# soapdis_schematic.net
KiCad netlist of a schematic drawn in EAGLE
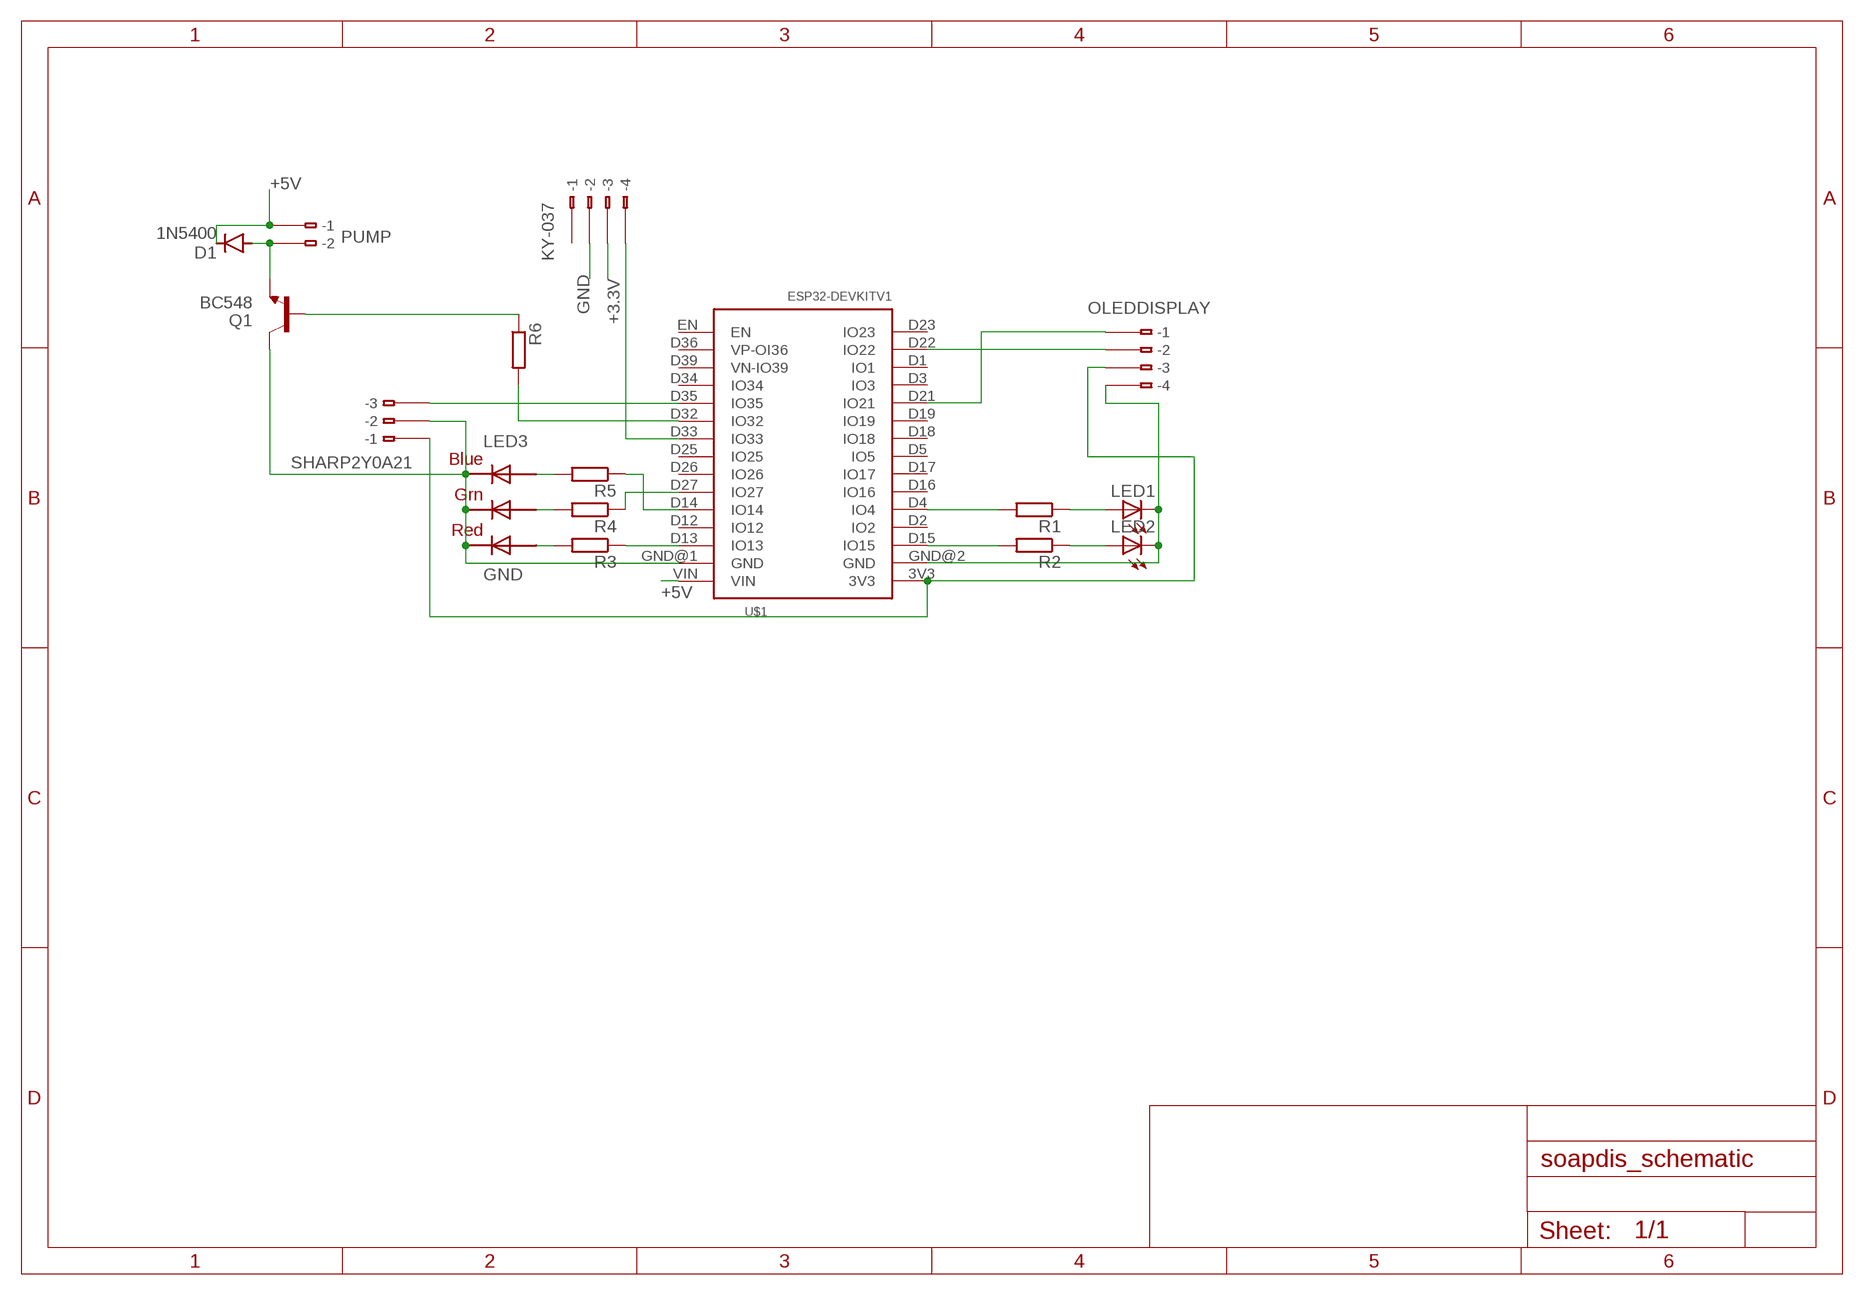
[diagram p0: schematic, sheet 1]

(export (version "E")
  (design (tool "Eeschema 10.0.6"))
  (components
    (comp (ref "D1")
      (value "1N5400")
      (footprint "eagle-import:DO201-15")
      (libsource (lib "eagle-import") (part "1N5400"))
    )
    (comp (ref "KY-037")
      (value "233-104")
      (footprint "eagle-import:233-104")
      (libsource (lib "eagle-import") (part "233-104"))
    )
    (comp (ref "LED1")
      (value "LED5MM")
      (footprint "eagle-import:LED5MM")
      (libsource (lib "eagle-import") (part "LED5MM"))
    )
    (comp (ref "LED2")
      (value "LED5MM")
      (footprint "eagle-import:LED5MM")
      (libsource (lib "eagle-import") (part "LED5MM"))
    )
    (comp (ref "LED3")
      (value "RGBLED5050")
      (footprint "eagle-import:RGBLED5050")
      (libsource (lib "eagle-import") (part "RGBLED5050"))
    )
    (comp (ref "OLEDDISPLAY")
      (value "233-104")
      (footprint "eagle-import:233-104")
      (libsource (lib "eagle-import") (part "233-104"))
    )
    (comp (ref "PUMP")
      (value "233-102")
      (footprint "eagle-import:233-102")
      (libsource (lib "eagle-import") (part "233-102"))
    )
    (comp (ref "Q1")
      (value "BC548")
      (footprint "eagle-import:TO92-EBC")
      (libsource (lib "eagle-import") (part "BC548"))
    )
    (comp (ref "R1")
      (value "R-EU_0204/7")
      (footprint "eagle-import:0204_7")
      (libsource (lib "eagle-import") (part "R-EU_0204/7"))
    )
    (comp (ref "R2")
      (value "R-EU_0204/7")
      (footprint "eagle-import:0204_7")
      (libsource (lib "eagle-import") (part "R-EU_0204/7"))
    )
    (comp (ref "R3")
      (value "R-EU_0204/7")
      (footprint "eagle-import:0204_7")
      (libsource (lib "eagle-import") (part "R-EU_0204/7"))
    )
    (comp (ref "R4")
      (value "R-EU_0204/7")
      (footprint "eagle-import:0204_7")
      (libsource (lib "eagle-import") (part "R-EU_0204/7"))
    )
    (comp (ref "R5")
      (value "R-EU_0204/7")
      (footprint "eagle-import:0204_7")
      (libsource (lib "eagle-import") (part "R-EU_0204/7"))
    )
    (comp (ref "R6")
      (value "R-EU_0204/7")
      (footprint "eagle-import:0204_7")
      (libsource (lib "eagle-import") (part "R-EU_0204/7"))
    )
    (comp (ref "SHARP2Y0A21")
      (value "233-103")
      (footprint "eagle-import:233-103")
      (libsource (lib "eagle-import") (part "233-103"))
    )
    (comp (ref "U$1")
      (value "ESP32DEVKITV1")
      (footprint "eagle-import:ESP32-DEVKITV1")
      (libsource (lib "eagle-import") (part "ESP32DEVKITV1"))
    )
  )
  (nets
    (net (code "1") (name "/+3.3V") (class "Default")
      (node (ref "KY-037") (pin "B3") (pinfunction "B-3_B3") (pintype "passive"))
    )
    (net (code "2") (name "/+5V") (class "Default")
      (node (ref "D1") (pin "C") (pinfunction "C_C") (pintype "passive"))
      (node (ref "PUMP") (pin "B1") (pinfunction "B-1_B1") (pintype "passive"))
      (node (ref "U$1") (pin "VIN") (pinfunction "VIN_VIN") (pintype "bidirectional"))
    )
    (net (code "3") (name "/GND") (class "Default")
      (node (ref "KY-037") (pin "B2") (pinfunction "B-2_B2") (pintype "passive"))
      (node (ref "LED3") (pin "4") (pinfunction "BLUE_C_4") (pintype "bidirectional"))
      (node (ref "LED3") (pin "5") (pinfunction "RED_C_5") (pintype "bidirectional"))
      (node (ref "LED3") (pin "6") (pinfunction "GREEN_C_6") (pintype "bidirectional"))
      (node (ref "Q1") (pin "C") (pinfunction "C_C") (pintype "passive"))
      (node (ref "SHARP2Y0A21") (pin "B2") (pinfunction "B-2_B2") (pintype "passive"))
      (node (ref "U$1") (pin "GND@1") (pinfunction "GND_GND@1") (pintype "bidirectional"))
    )
    (net (code "4") (name "Net-(KY-037-B-4)") (class "Default")
      (node (ref "KY-037") (pin "B4") (pinfunction "B-4_B4") (pintype "passive"))
      (node (ref "U$1") (pin "D33") (pinfunction "IO33_D33") (pintype "bidirectional"))
    )
    (net (code "5") (name "Net-(LED1-C)") (class "Default")
      (node (ref "LED1") (pin "K") (pinfunction "C_K") (pintype "passive"))
      (node (ref "LED2") (pin "K") (pinfunction "C_K") (pintype "passive"))
      (node (ref "OLEDDISPLAY") (pin "B4") (pinfunction "B-4_B4") (pintype "passive"))
      (node (ref "U$1") (pin "GND@2") (pinfunction "GND_GND@2") (pintype "bidirectional"))
    )
    (net (code "6") (name "Net-(LED1-PadA)") (class "Default")
      (node (ref "LED1") (pin "A") (pinfunction "A_A") (pintype "passive"))
      (node (ref "R1") (pin "1") (pinfunction "1_1") (pintype "passive"))
    )
    (net (code "7") (name "Net-(LED2-PadA)") (class "Default")
      (node (ref "LED2") (pin "A") (pinfunction "A_A") (pintype "passive"))
      (node (ref "R2") (pin "1") (pinfunction "1_1") (pintype "passive"))
    )
    (net (code "8") (name "Net-(LED3-BLUE_A)") (class "Default")
      (node (ref "LED3") (pin "3") (pinfunction "BLUE_A_3") (pintype "bidirectional"))
      (node (ref "R5") (pin "2") (pinfunction "2_2") (pintype "passive"))
    )
    (net (code "9") (name "Net-(LED3-GREEN_A)") (class "Default")
      (node (ref "LED3") (pin "1") (pinfunction "GREEN_A_1") (pintype "bidirectional"))
      (node (ref "R4") (pin "2") (pinfunction "2_2") (pintype "passive"))
    )
    (net (code "10") (name "Net-(LED3-RED_A)") (class "Default")
      (node (ref "LED3") (pin "2") (pinfunction "RED_A_2") (pintype "bidirectional"))
      (node (ref "R3") (pin "2") (pinfunction "2_2") (pintype "passive"))
    )
    (net (code "11") (name "Net-(OLEDDISPLAY-B-1)") (class "Default")
      (node (ref "OLEDDISPLAY") (pin "B1") (pinfunction "B-1_B1") (pintype "passive"))
      (node (ref "U$1") (pin "D21") (pinfunction "IO21_D21") (pintype "bidirectional"))
    )
    (net (code "12") (name "Net-(OLEDDISPLAY-B-2)") (class "Default")
      (node (ref "OLEDDISPLAY") (pin "B2") (pinfunction "B-2_B2") (pintype "passive"))
      (node (ref "U$1") (pin "D22") (pinfunction "IO22_D22") (pintype "bidirectional"))
    )
    (net (code "13") (name "Net-(OLEDDISPLAY-B-3)") (class "Default")
      (node (ref "OLEDDISPLAY") (pin "B3") (pinfunction "B-3_B3") (pintype "passive"))
      (node (ref "SHARP2Y0A21") (pin "B1") (pinfunction "B-1_B1") (pintype "passive"))
      (node (ref "U$1") (pin "3V3") (pinfunction "3V3_3V3") (pintype "bidirectional"))
    )
    (net (code "14") (name "Net-(PUMP-B-2)") (class "Default")
      (node (ref "D1") (pin "A") (pinfunction "A_A") (pintype "passive"))
      (node (ref "PUMP") (pin "B2") (pinfunction "B-2_B2") (pintype "passive"))
      (node (ref "Q1") (pin "E") (pinfunction "E_E") (pintype "passive"))
    )
    (net (code "15") (name "Net-(Q1-PadB)") (class "Default")
      (node (ref "Q1") (pin "B") (pinfunction "B_B") (pintype "passive"))
      (node (ref "R6") (pin "1") (pinfunction "1_1") (pintype "passive"))
    )
    (net (code "16") (name "Net-(SHARP2Y0A21-B-3)") (class "Default")
      (node (ref "SHARP2Y0A21") (pin "B3") (pinfunction "B-3_B3") (pintype "passive"))
      (node (ref "U$1") (pin "D35") (pinfunction "IO35_D35") (pintype "bidirectional"))
    )
    (net (code "17") (name "Net-(U$1-IO4)") (class "Default")
      (node (ref "R1") (pin "2") (pinfunction "2_2") (pintype "passive"))
      (node (ref "U$1") (pin "D4") (pinfunction "IO4_D4") (pintype "bidirectional"))
    )
    (net (code "18") (name "Net-(U$1-IO13)") (class "Default")
      (node (ref "R3") (pin "1") (pinfunction "1_1") (pintype "passive"))
      (node (ref "U$1") (pin "D13") (pinfunction "IO13_D13") (pintype "bidirectional"))
    )
    (net (code "19") (name "Net-(U$1-IO14)") (class "Default")
      (node (ref "R5") (pin "1") (pinfunction "1_1") (pintype "passive"))
      (node (ref "U$1") (pin "D14") (pinfunction "IO14_D14") (pintype "bidirectional"))
    )
    (net (code "20") (name "Net-(U$1-IO15)") (class "Default")
      (node (ref "R2") (pin "2") (pinfunction "2_2") (pintype "passive"))
      (node (ref "U$1") (pin "D15") (pinfunction "IO15_D15") (pintype "bidirectional"))
    )
    (net (code "21") (name "Net-(U$1-IO27)") (class "Default")
      (node (ref "R4") (pin "1") (pinfunction "1_1") (pintype "passive"))
      (node (ref "U$1") (pin "D27") (pinfunction "IO27_D27") (pintype "bidirectional"))
    )
    (net (code "22") (name "Net-(U$1-IO32)") (class "Default")
      (node (ref "R6") (pin "2") (pinfunction "2_2") (pintype "passive"))
      (node (ref "U$1") (pin "D32") (pinfunction "IO32_D32") (pintype "bidirectional"))
    )
    (net (code "23") (name "unconnected-(KY-037--1-PadA1)") (class "Default")
      (node (ref "KY-037") (pin "A1") (pinfunction "-1_A1") (pintype "passive"))
    )
    (net (code "24") (name "unconnected-(KY-037--2-PadA2)") (class "Default")
      (node (ref "KY-037") (pin "A2") (pinfunction "-2_A2") (pintype "passive"))
    )
    (net (code "25") (name "unconnected-(KY-037--3-PadA3)") (class "Default")
      (node (ref "KY-037") (pin "A3") (pinfunction "-3_A3") (pintype "passive"))
    )
    (net (code "26") (name "unconnected-(KY-037--4-PadA4)") (class "Default")
      (node (ref "KY-037") (pin "A4") (pinfunction "-4_A4") (pintype "passive"))
    )
    (net (code "27") (name "unconnected-(KY-037-B-1-PadB1)") (class "Default")
      (node (ref "KY-037") (pin "B1") (pinfunction "B-1_B1") (pintype "passive"))
    )
    (net (code "28") (name "unconnected-(OLEDDISPLAY--1-PadA1)") (class "Default")
      (node (ref "OLEDDISPLAY") (pin "A1") (pinfunction "-1_A1") (pintype "passive"))
    )
    (net (code "29") (name "unconnected-(OLEDDISPLAY--2-PadA2)") (class "Default")
      (node (ref "OLEDDISPLAY") (pin "A2") (pinfunction "-2_A2") (pintype "passive"))
    )
    (net (code "30") (name "unconnected-(OLEDDISPLAY--3-PadA3)") (class "Default")
      (node (ref "OLEDDISPLAY") (pin "A3") (pinfunction "-3_A3") (pintype "passive"))
    )
    (net (code "31") (name "unconnected-(OLEDDISPLAY--4-PadA4)") (class "Default")
      (node (ref "OLEDDISPLAY") (pin "A4") (pinfunction "-4_A4") (pintype "passive"))
    )
    (net (code "32") (name "unconnected-(PUMP--1-PadA1)") (class "Default")
      (node (ref "PUMP") (pin "A1") (pinfunction "-1_A1") (pintype "passive"))
    )
    (net (code "33") (name "unconnected-(PUMP--2-PadA2)") (class "Default")
      (node (ref "PUMP") (pin "A2") (pinfunction "-2_A2") (pintype "passive"))
    )
    (net (code "34") (name "unconnected-(SHARP2Y0A21--1-PadA1)") (class "Default")
      (node (ref "SHARP2Y0A21") (pin "A1") (pinfunction "-1_A1") (pintype "passive"))
    )
    (net (code "35") (name "unconnected-(SHARP2Y0A21--2-PadA2)") (class "Default")
      (node (ref "SHARP2Y0A21") (pin "A2") (pinfunction "-2_A2") (pintype "passive"))
    )
    (net (code "36") (name "unconnected-(SHARP2Y0A21--3-PadA3)") (class "Default")
      (node (ref "SHARP2Y0A21") (pin "A3") (pinfunction "-3_A3") (pintype "passive"))
    )
    (net (code "37") (name "unconnected-(U$1-IO1-PadD1)") (class "Default")
      (node (ref "U$1") (pin "D1") (pinfunction "IO1_D1") (pintype "bidirectional"))
    )
    (net (code "38") (name "unconnected-(U$1-IO2-PadD2)") (class "Default")
      (node (ref "U$1") (pin "D2") (pinfunction "IO2_D2") (pintype "bidirectional"))
    )
    (net (code "39") (name "unconnected-(U$1-IO3-PadD3)") (class "Default")
      (node (ref "U$1") (pin "D3") (pinfunction "IO3_D3") (pintype "bidirectional"))
    )
    (net (code "40") (name "unconnected-(U$1-IO5-PadD5)") (class "Default")
      (node (ref "U$1") (pin "D5") (pinfunction "IO5_D5") (pintype "bidirectional"))
    )
    (net (code "41") (name "unconnected-(U$1-IO12-PadD12)") (class "Default")
      (node (ref "U$1") (pin "D12") (pinfunction "IO12_D12") (pintype "bidirectional"))
    )
    (net (code "42") (name "unconnected-(U$1-IO16-PadD16)") (class "Default")
      (node (ref "U$1") (pin "D16") (pinfunction "IO16_D16") (pintype "bidirectional"))
    )
    (net (code "43") (name "unconnected-(U$1-IO17-PadD17)") (class "Default")
      (node (ref "U$1") (pin "D17") (pinfunction "IO17_D17") (pintype "bidirectional"))
    )
    (net (code "44") (name "unconnected-(U$1-IO18-PadD18)") (class "Default")
      (node (ref "U$1") (pin "D18") (pinfunction "IO18_D18") (pintype "bidirectional"))
    )
    (net (code "45") (name "unconnected-(U$1-IO19-PadD19)") (class "Default")
      (node (ref "U$1") (pin "D19") (pinfunction "IO19_D19") (pintype "bidirectional"))
    )
    (net (code "46") (name "unconnected-(U$1-IO23-PadD23)") (class "Default")
      (node (ref "U$1") (pin "D23") (pinfunction "IO23_D23") (pintype "bidirectional"))
    )
    (net (code "47") (name "unconnected-(U$1-IO25-PadD25)") (class "Default")
      (node (ref "U$1") (pin "D25") (pinfunction "IO25_D25") (pintype "bidirectional"))
    )
    (net (code "48") (name "unconnected-(U$1-IO26-PadD26)") (class "Default")
      (node (ref "U$1") (pin "D26") (pinfunction "IO26_D26") (pintype "bidirectional"))
    )
    (net (code "49") (name "unconnected-(U$1-IO34-PadD34)") (class "Default")
      (node (ref "U$1") (pin "D34") (pinfunction "IO34_D34") (pintype "bidirectional"))
    )
    (net (code "50") (name "unconnected-(U$1-PadEN)") (class "Default")
      (node (ref "U$1") (pin "EN") (pinfunction "EN_EN") (pintype "bidirectional"))
    )
    (net (code "51") (name "unconnected-(U$1-VN-IO39-PadD39)") (class "Default")
      (node (ref "U$1") (pin "D39") (pinfunction "VN-IO39_D39") (pintype "bidirectional"))
    )
    (net (code "52") (name "unconnected-(U$1-VP-OI36-PadD36)") (class "Default")
      (node (ref "U$1") (pin "D36") (pinfunction "VP-OI36_D36") (pintype "bidirectional"))
    )
  )
)
